# cpu.net
KiCad netlist of a schematic drawn in Altium Designer
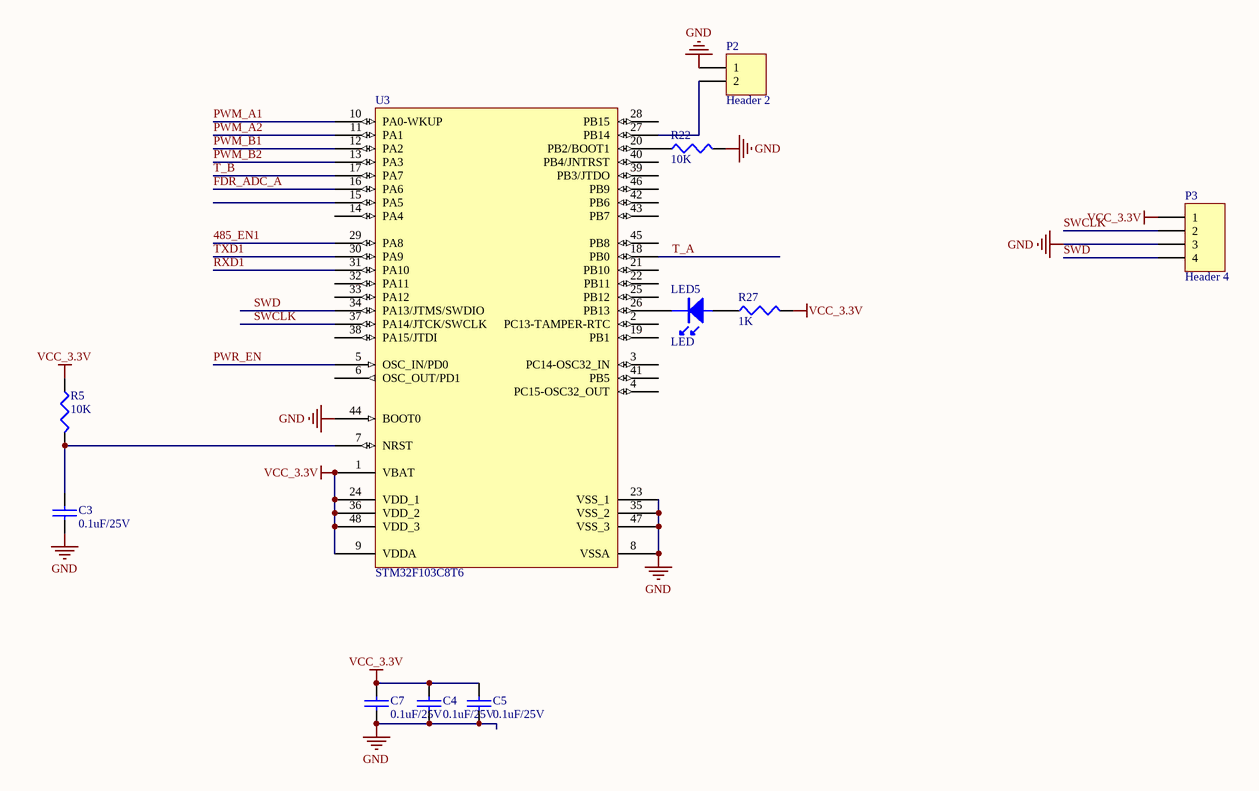
[diagram p0: cpu.SchDoc]

(export (version "E")
  (design (tool "Eeschema 10.0.6"))
  (components
    (comp (ref "C3")
      (value "0.1uF/25V")
      (footprint "0603C")
      (description "Capacitor")
      (libsource (lib "SM") (part "CAP"))
    )
    (comp (ref "C4")
      (value "0.1uF/25V")
      (footprint "0603C")
      (description "Capacitor")
      (libsource (lib "SM") (part "CAP"))
    )
    (comp (ref "C5")
      (value "0.1uF/25V")
      (footprint "0603C")
      (description "Capacitor")
      (libsource (lib "SM") (part "CAP"))
    )
    (comp (ref "C7")
      (value "0.1uF/25V")
      (footprint "0603C")
      (description "Capacitor")
      (libsource (lib "SM") (part "CAP"))
    )
    (comp (ref "LED5") (value "LED") (footprint "0603LED") (libsource (lib "我的元件库") (part "LED")))
    (comp (ref "P2")
      (value "Header 2")
      (footprint "HDR1X2")
      (description "Header, 2-Pin")
      (fields (field (name "PUBLISHER") "Altium Limited"))
      (libsource (lib "Miscellaneous Connectors") (part "Header 2"))
    )
    (comp (ref "P3")
      (value "Header 4")
      (footprint "HDR1X4")
      (description "Header, 4-Pin")
      (fields (field (name "PUBLISHER") "Altium Limited"))
      (libsource (lib "Miscellaneous Connectors") (part "Header 4"))
    )
    (comp (ref "R5")
      (value "10K")
      (footprint "0603R")
      (description "Resistor")
      (fields (field (name "PUBLISHER") "Altium Limited"))
      (libsource (lib "SM") (part "Res3"))
    )
    (comp (ref "R22")
      (value "10K")
      (footprint "0603R")
      (description "Resistor")
      (fields (field (name "PUBLISHER") "Altium Limited"))
      (libsource (lib "SM") (part "Res3"))
    )
    (comp (ref "R27")
      (value "1K")
      (footprint "0603R")
      (libsource (lib "ZWLIntegrated_Library") (part "RES1"))
    )
    (comp (ref "U3")
      (value "STM32F103C8T6")
      (footprint "TQFP-48")
      (description "STM32 ARM-based 32-bit MCU with 64 Kbytes Flash, 48-pin LQFP, Industrial Temperature")
      (fields (field (name "PUBLISHER") "Altium Limited"))
      (libsource (lib "ST Microcontroller 32-Bit STM32") (part "STM32F103C8T6"))
    )
  )
  (nets
    (net (code "1") (name "/485_EN1") (class "Default")
      (node (ref "U3") (pin "29") (pinfunction "PA8_29") (pintype "bidirectional"))
    )
    (net (code "2") (name "/FDR_ADC_A") (class "Default")
      (node (ref "U3") (pin "16") (pinfunction "PA6_16") (pintype "bidirectional"))
    )
    (net (code "3") (name "/PWM_A1") (class "Default")
      (node (ref "U3") (pin "10") (pinfunction "PA0-WKUP_10") (pintype "bidirectional"))
    )
    (net (code "4") (name "/PWM_A2") (class "Default")
      (node (ref "U3") (pin "11") (pinfunction "PA1_11") (pintype "bidirectional"))
    )
    (net (code "5") (name "/PWM_B1") (class "Default")
      (node (ref "U3") (pin "12") (pinfunction "PA2_12") (pintype "bidirectional"))
    )
    (net (code "6") (name "/PWM_B2") (class "Default")
      (node (ref "U3") (pin "13") (pinfunction "PA3_13") (pintype "bidirectional"))
    )
    (net (code "7") (name "/PWR_EN") (class "Default")
      (node (ref "U3") (pin "5") (pinfunction "OSC_IN/PD0_5") (pintype "input"))
    )
    (net (code "8") (name "/RXD1") (class "Default")
      (node (ref "U3") (pin "31") (pinfunction "PA10_31") (pintype "bidirectional"))
    )
    (net (code "9") (name "/SWCLK") (class "Default")
      (node (ref "P3") (pin "2") (pinfunction "2_2") (pintype "passive"))
      (node (ref "U3") (pin "37") (pinfunction "PA14/JTCK/SWCLK_37") (pintype "bidirectional"))
    )
    (net (code "10") (name "/SWD") (class "Default")
      (node (ref "P3") (pin "4") (pinfunction "4_4") (pintype "passive"))
      (node (ref "U3") (pin "34") (pinfunction "PA13/JTMS/SWDIO_34") (pintype "bidirectional"))
    )
    (net (code "11") (name "/TXD1") (class "Default")
      (node (ref "U3") (pin "30") (pinfunction "PA9_30") (pintype "bidirectional"))
    )
    (net (code "12") (name "/T_A") (class "Default")
      (node (ref "U3") (pin "18") (pinfunction "PB0_18") (pintype "bidirectional"))
    )
    (net (code "13") (name "/T_B") (class "Default")
      (node (ref "U3") (pin "17") (pinfunction "PA7_17") (pintype "bidirectional"))
    )
    (net (code "14") (name "GND") (class "Default")
      (node (ref "C3") (pin "1") (pinfunction "1_1") (pintype "passive"))
      (node (ref "C4") (pin "1") (pinfunction "1_1") (pintype "passive"))
      (node (ref "C5") (pin "1") (pinfunction "1_1") (pintype "passive"))
      (node (ref "C7") (pin "1") (pinfunction "1_1") (pintype "passive"))
      (node (ref "P2") (pin "1") (pinfunction "1_1") (pintype "passive"))
      (node (ref "P3") (pin "3") (pinfunction "3_3") (pintype "passive"))
      (node (ref "R22") (pin "2") (pinfunction "2_2") (pintype "passive"))
      (node (ref "U3") (pin "23") (pinfunction "VSS_1_23") (pintype "power_in"))
      (node (ref "U3") (pin "35") (pinfunction "VSS_2_35") (pintype "power_in"))
      (node (ref "U3") (pin "44") (pinfunction "BOOT0_44") (pintype "input"))
      (node (ref "U3") (pin "47") (pinfunction "VSS_3_47") (pintype "power_in"))
      (node (ref "U3") (pin "8") (pinfunction "VSSA_8") (pintype "power_in"))
    )
    (net (code "15") (name "Net-(LED5-Pad1)") (class "Default")
      (node (ref "LED5") (pin "1") (pinfunction "1_1") (pintype "passive"))
      (node (ref "R27") (pin "1") (pinfunction "1_1") (pintype "passive"))
    )
    (net (code "16") (name "Net-(U3-NRST)") (class "Default")
      (node (ref "C3") (pin "2") (pinfunction "2_2") (pintype "passive"))
      (node (ref "R5") (pin "2") (pinfunction "2_2") (pintype "passive"))
      (node (ref "U3") (pin "7") (pinfunction "NRST_7") (pintype "bidirectional"))
    )
    (net (code "17") (name "Net-(U3-PB2{slash}BOOT1)") (class "Default")
      (node (ref "R22") (pin "1") (pinfunction "1_1") (pintype "passive"))
      (node (ref "U3") (pin "20") (pinfunction "PB2/BOOT1_20") (pintype "bidirectional"))
    )
    (net (code "18") (name "Net-(U3-PB13)") (class "Default")
      (node (ref "LED5") (pin "2") (pinfunction "2_2") (pintype "passive"))
      (node (ref "U3") (pin "26") (pinfunction "PB13_26") (pintype "bidirectional"))
    )
    (net (code "19") (name "Net-(U3-PB14)") (class "Default")
      (node (ref "P2") (pin "2") (pinfunction "2_2") (pintype "passive"))
      (node (ref "U3") (pin "27") (pinfunction "PB14_27") (pintype "bidirectional"))
    )
    (net (code "20") (name "VCC_3.3V") (class "Default")
      (node (ref "C4") (pin "2") (pinfunction "2_2") (pintype "passive"))
      (node (ref "C5") (pin "2") (pinfunction "2_2") (pintype "passive"))
      (node (ref "C7") (pin "2") (pinfunction "2_2") (pintype "passive"))
      (node (ref "P3") (pin "1") (pinfunction "1_1") (pintype "passive"))
      (node (ref "R27") (pin "2") (pinfunction "2_2") (pintype "passive"))
      (node (ref "R5") (pin "1") (pinfunction "1_1") (pintype "passive"))
      (node (ref "U3") (pin "1") (pinfunction "VBAT_1") (pintype "power_in"))
      (node (ref "U3") (pin "24") (pinfunction "VDD_1_24") (pintype "power_in"))
      (node (ref "U3") (pin "36") (pinfunction "VDD_2_36") (pintype "power_in"))
      (node (ref "U3") (pin "48") (pinfunction "VDD_3_48") (pintype "power_in"))
      (node (ref "U3") (pin "9") (pinfunction "VDDA_9") (pintype "power_in"))
    )
    (net (code "21") (name "unconnected-(U3-OSC_OUT{slash}PD1-Pad6)") (class "Default")
      (node (ref "U3") (pin "6") (pinfunction "OSC_OUT/PD1_6") (pintype "output"))
    )
    (net (code "22") (name "unconnected-(U3-PA4-Pad14)") (class "Default")
      (node (ref "U3") (pin "14") (pinfunction "PA4_14") (pintype "bidirectional"))
    )
    (net (code "23") (name "unconnected-(U3-PA5-Pad15)") (class "Default")
      (node (ref "U3") (pin "15") (pinfunction "PA5_15") (pintype "bidirectional"))
    )
    (net (code "24") (name "unconnected-(U3-PA11-Pad32)") (class "Default")
      (node (ref "U3") (pin "32") (pinfunction "PA11_32") (pintype "bidirectional"))
    )
    (net (code "25") (name "unconnected-(U3-PA12-Pad33)") (class "Default")
      (node (ref "U3") (pin "33") (pinfunction "PA12_33") (pintype "bidirectional"))
    )
    (net (code "26") (name "unconnected-(U3-PA15{slash}JTDI-Pad38)") (class "Default")
      (node (ref "U3") (pin "38") (pinfunction "PA15/JTDI_38") (pintype "bidirectional"))
    )
    (net (code "27") (name "unconnected-(U3-PB1-Pad19)") (class "Default")
      (node (ref "U3") (pin "19") (pinfunction "PB1_19") (pintype "bidirectional"))
    )
    (net (code "28") (name "unconnected-(U3-PB3{slash}JTDO-Pad39)") (class "Default")
      (node (ref "U3") (pin "39") (pinfunction "PB3/JTDO_39") (pintype "bidirectional"))
    )
    (net (code "29") (name "unconnected-(U3-PB4{slash}JNTRST-Pad40)") (class "Default")
      (node (ref "U3") (pin "40") (pinfunction "PB4/JNTRST_40") (pintype "bidirectional"))
    )
    (net (code "30") (name "unconnected-(U3-PB5-Pad41)") (class "Default")
      (node (ref "U3") (pin "41") (pinfunction "PB5_41") (pintype "bidirectional"))
    )
    (net (code "31") (name "unconnected-(U3-PB6-Pad42)") (class "Default")
      (node (ref "U3") (pin "42") (pinfunction "PB6_42") (pintype "bidirectional"))
    )
    (net (code "32") (name "unconnected-(U3-PB7-Pad43)") (class "Default")
      (node (ref "U3") (pin "43") (pinfunction "PB7_43") (pintype "bidirectional"))
    )
    (net (code "33") (name "unconnected-(U3-PB8-Pad45)") (class "Default")
      (node (ref "U3") (pin "45") (pinfunction "PB8_45") (pintype "bidirectional"))
    )
    (net (code "34") (name "unconnected-(U3-PB9-Pad46)") (class "Default")
      (node (ref "U3") (pin "46") (pinfunction "PB9_46") (pintype "bidirectional"))
    )
    (net (code "35") (name "unconnected-(U3-PB10-Pad21)") (class "Default")
      (node (ref "U3") (pin "21") (pinfunction "PB10_21") (pintype "bidirectional"))
    )
    (net (code "36") (name "unconnected-(U3-PB11-Pad22)") (class "Default")
      (node (ref "U3") (pin "22") (pinfunction "PB11_22") (pintype "bidirectional"))
    )
    (net (code "37") (name "unconnected-(U3-PB12-Pad25)") (class "Default")
      (node (ref "U3") (pin "25") (pinfunction "PB12_25") (pintype "bidirectional"))
    )
    (net (code "38") (name "unconnected-(U3-PB15-Pad28)") (class "Default")
      (node (ref "U3") (pin "28") (pinfunction "PB15_28") (pintype "bidirectional"))
    )
    (net (code "39") (name "unconnected-(U3-PC13-TAMPER-RTC-Pad2)") (class "Default")
      (node (ref "U3") (pin "2") (pinfunction "PC13-TAMPER-RTC_2") (pintype "bidirectional"))
    )
    (net (code "40") (name "unconnected-(U3-PC14-OSC32_IN-Pad3)") (class "Default")
      (node (ref "U3") (pin "3") (pinfunction "PC14-OSC32_IN_3") (pintype "bidirectional"))
    )
    (net (code "41") (name "unconnected-(U3-PC15-OSC32_OUT-Pad4)") (class "Default")
      (node (ref "U3") (pin "4") (pinfunction "PC15-OSC32_OUT_4") (pintype "bidirectional"))
    )
  )
)
